# ColorDisplay.net
KiCad netlist of a schematic drawn in EAGLE
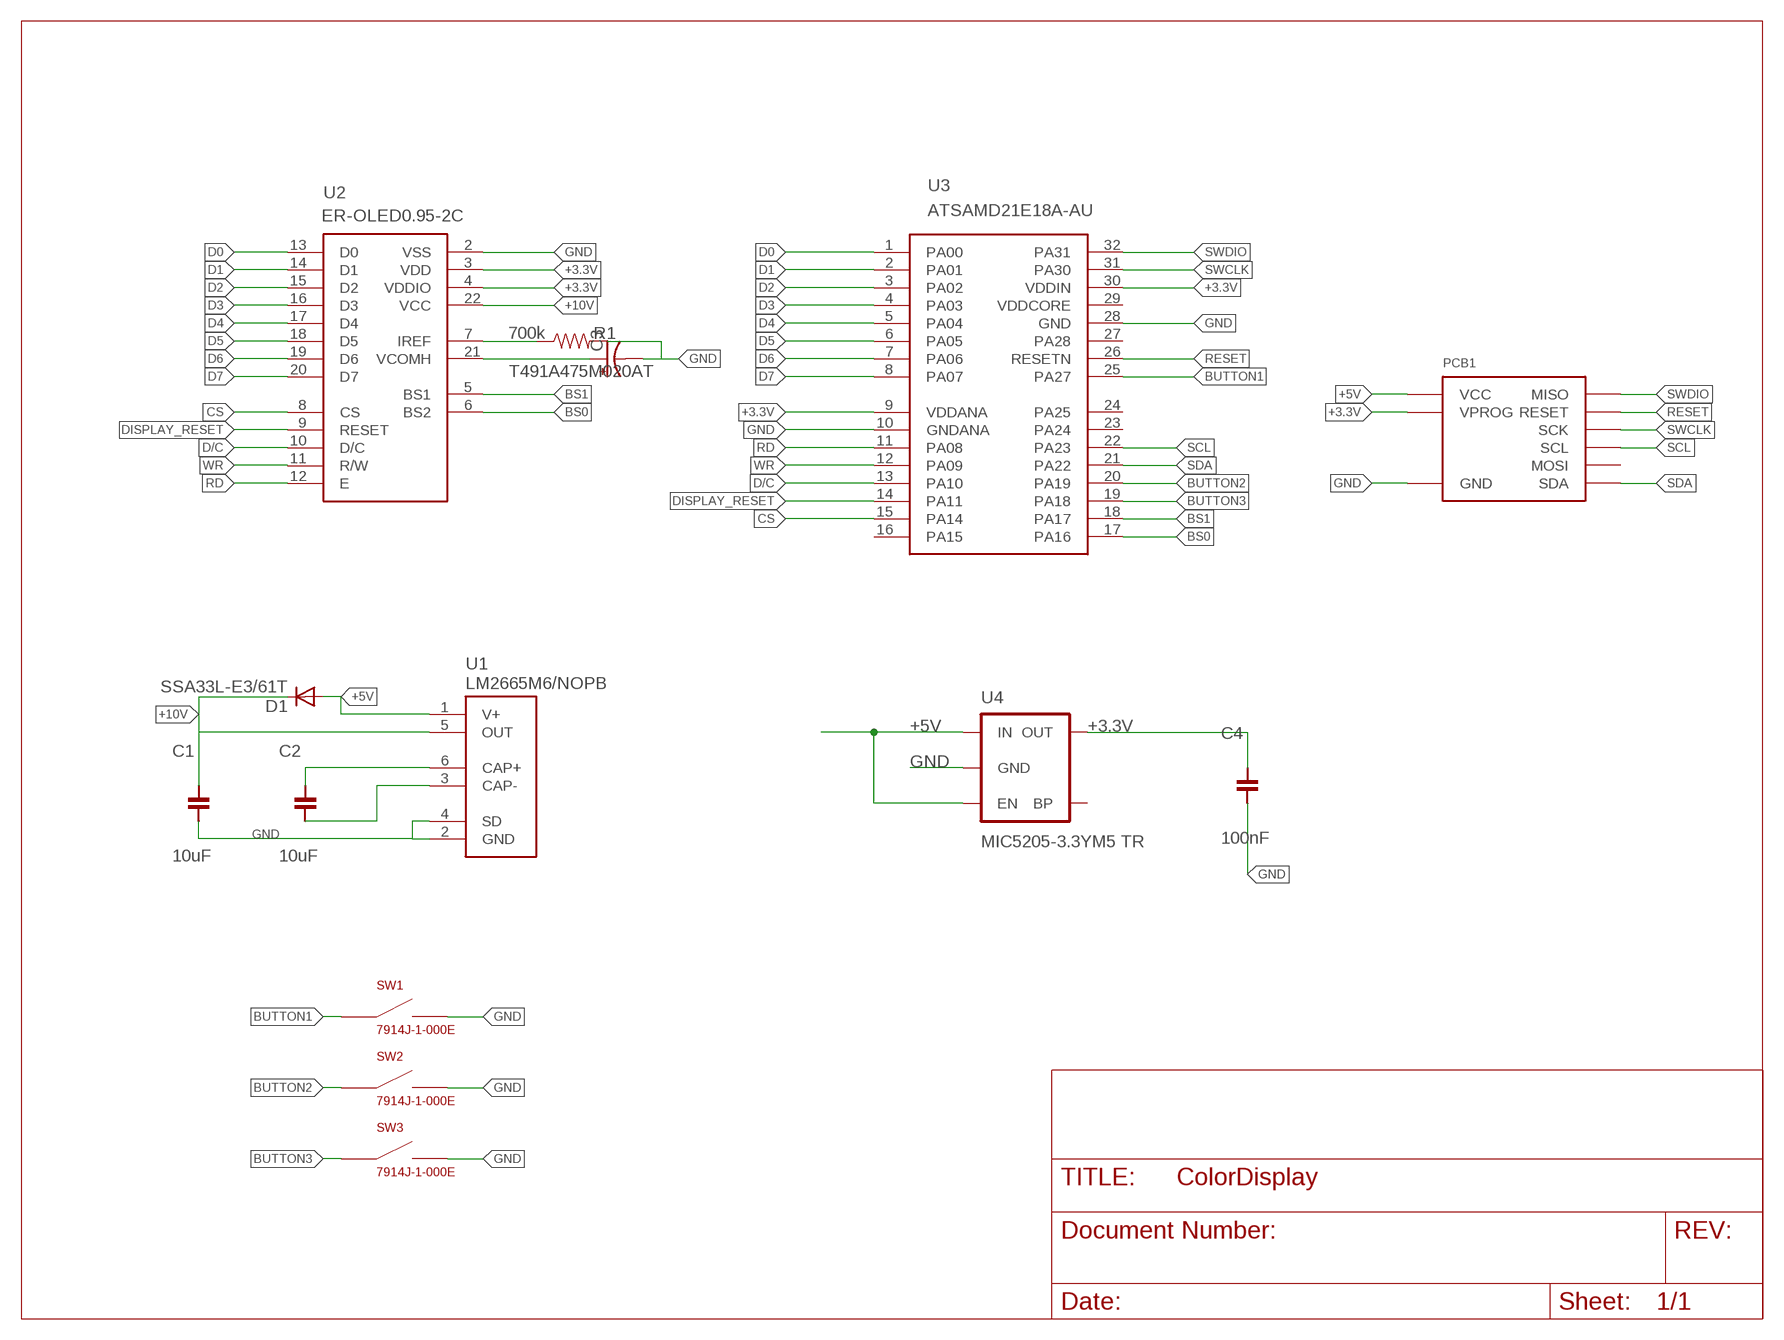
[diagram p0: schematic, sheet 1]

(export (version "E")
  (design (tool "Eeschema 10.0.6"))
  (components
    (comp (ref "C1")
      (value "10uF")
      (footprint "eagle-import:C1206")
      (fields (field (name "PARTNUM") "CL31A106KAHNNNE"))
      (libsource (lib "eagle-import") (part "CAPACITOR-10UF-1206"))
    )
    (comp (ref "C2")
      (value "10uF")
      (footprint "eagle-import:C1206")
      (fields (field (name "PARTNUM") "CL31A106KAHNNNE"))
      (libsource (lib "eagle-import") (part "CAPACITOR-10UF-1206"))
    )
    (comp (ref "C3")
      (value "T491A475M020AT")
      (footprint "eagle-import:EIA3216")
      (libsource (lib "eagle-import") (part "10UF-16V-10%(TANT)"))
    )
    (comp (ref "C4")
      (value "100nF")
      (footprint "eagle-import:0603")
      (fields (field (name "PARTNUM") "C0603C104K5RACTU"))
      (libsource (lib "eagle-import") (part "CAPACITOR-100NF"))
    )
    (comp (ref "D1")
      (value "SSA33L-E3/61T")
      (footprint "eagle-import:SMA-DIODE")
      (libsource (lib "eagle-import") (part "DIODESMA"))
    )
    (comp (ref "PCB1")
      (value "DEVICE-PCB-TABS")
      (footprint "eagle-import:DEVICE-PCB-TABS")
      (fields (field (name "BOARD") "Display") (field (name "VERSION") "2"))
      (libsource (lib "eagle-import") (part "DEVICE-PCB-TABS"))
    )
    (comp (ref "R1")
      (value "700k")
      (footprint "eagle-import:0603")
      (libsource (lib "eagle-import") (part "RESISTOR-0603"))
    )
    (comp (ref "SW1")
      (value "7914J-1-000E")
      (footprint "eagle-import:BOURNS-7914J")
      (libsource (lib "eagle-import") (part "SWITCHBOURNS-7914J"))
    )
    (comp (ref "SW2")
      (value "7914J-1-000E")
      (footprint "eagle-import:BOURNS-7914J")
      (libsource (lib "eagle-import") (part "SWITCHBOURNS-7914J"))
    )
    (comp (ref "SW3")
      (value "7914J-1-000E")
      (footprint "eagle-import:BOURNS-7914J")
      (libsource (lib "eagle-import") (part "SWITCHBOURNS-7914J"))
    )
    (comp (ref "U1")
      (value "LM2665M6/NOPB")
      (footprint "eagle-import:SOT-26")
      (libsource (lib "eagle-import") (part "LM2665"))
    )
    (comp (ref "U2")
      (value "ER-OLED0.95-2C")
      (footprint "eagle-import:FPC-24-REVERSE")
      (fields (field (name "MANUFACTURER") "buydisplay.com"))
      (libsource (lib "eagle-import") (part "OLED-COLORREVERSE"))
    )
    (comp (ref "U3")
      (value "ATSAMD21E18A-AU")
      (footprint "eagle-import:TQFP-32")
      (libsource (lib "eagle-import") (part "SAMD21E"))
    )
    (comp (ref "U4")
      (value "MIC5205-3.3YM5 TR")
      (footprint "eagle-import:SOT23-5")
      (libsource (lib "eagle-import") (part "VREG-MIC5205-3.3V"))
    )
  )
  (nets
    (net (code "1") (name "+3.3V") (class "Default")
      (node (ref "C4") (pin "1") (pinfunction "1_1") (pintype "passive"))
      (node (ref "PCB1") (pin "PROG0") (pinfunction "VPROG_PROG0") (pintype "bidirectional"))
      (node (ref "U2") (pin "3") (pinfunction "VDD_3") (pintype "bidirectional"))
      (node (ref "U2") (pin "4") (pinfunction "VDDIO_4") (pintype "bidirectional"))
      (node (ref "U3") (pin "30") (pinfunction "VDDIN_30") (pintype "bidirectional"))
      (node (ref "U3") (pin "9") (pinfunction "VDDANA_9") (pintype "bidirectional"))
      (node (ref "U4") (pin "5") (pinfunction "OUT_5") (pintype "passive"))
    )
    (net (code "2") (name "+5V") (class "Default")
      (node (ref "D1") (pin "A") (pinfunction "A_A") (pintype "passive"))
      (node (ref "PCB1") (pin "BUS2") (pinfunction "VCC_BUS2") (pintype "bidirectional"))
      (node (ref "U1") (pin "1") (pinfunction "V+_1") (pintype "bidirectional"))
      (node (ref "U4") (pin "1") (pinfunction "IN_1") (pintype "input"))
      (node (ref "U4") (pin "3") (pinfunction "EN_3") (pintype "input"))
    )
    (net (code "3") (name "+10V") (class "Default")
      (node (ref "C1") (pin "1") (pinfunction "1_1") (pintype "passive"))
      (node (ref "D1") (pin "C") (pinfunction "C_C") (pintype "passive"))
      (node (ref "U1") (pin "5") (pinfunction "OUT_5") (pintype "bidirectional"))
      (node (ref "U2") (pin "22") (pinfunction "VCC_22") (pintype "bidirectional"))
    )
    (net (code "4") (name "BS0") (class "Default")
      (node (ref "U2") (pin "6") (pinfunction "BS2_6") (pintype "bidirectional"))
      (node (ref "U3") (pin "17") (pinfunction "PA16_17") (pintype "bidirectional"))
    )
    (net (code "5") (name "BS1") (class "Default")
      (node (ref "U2") (pin "5") (pinfunction "BS1_5") (pintype "bidirectional"))
      (node (ref "U3") (pin "18") (pinfunction "PA17_18") (pintype "bidirectional"))
    )
    (net (code "6") (name "BUTTON1") (class "Default")
      (node (ref "SW1") (pin "POS$1") (pinfunction "POS1_POS$1") (pintype "bidirectional"))
      (node (ref "SW1") (pin "POS$2") (pinfunction "POS1_POS$2") (pintype "bidirectional"))
      (node (ref "U3") (pin "25") (pinfunction "PA27_25") (pintype "bidirectional"))
    )
    (net (code "7") (name "BUTTON2") (class "Default")
      (node (ref "SW2") (pin "POS$1") (pinfunction "POS1_POS$1") (pintype "bidirectional"))
      (node (ref "SW2") (pin "POS$2") (pinfunction "POS1_POS$2") (pintype "bidirectional"))
      (node (ref "U3") (pin "20") (pinfunction "PA19_20") (pintype "bidirectional"))
    )
    (net (code "8") (name "BUTTON3") (class "Default")
      (node (ref "SW3") (pin "POS$1") (pinfunction "POS1_POS$1") (pintype "bidirectional"))
      (node (ref "SW3") (pin "POS$2") (pinfunction "POS1_POS$2") (pintype "bidirectional"))
      (node (ref "U3") (pin "19") (pinfunction "PA18_19") (pintype "bidirectional"))
    )
    (net (code "9") (name "CS") (class "Default")
      (node (ref "U2") (pin "8") (pinfunction "CS_8") (pintype "bidirectional"))
      (node (ref "U3") (pin "15") (pinfunction "PA14_15") (pintype "bidirectional"))
    )
    (net (code "10") (name "D0") (class "Default")
      (node (ref "U2") (pin "13") (pinfunction "D0_13") (pintype "bidirectional"))
      (node (ref "U3") (pin "1") (pinfunction "PA00_1") (pintype "bidirectional"))
    )
    (net (code "11") (name "D1") (class "Default")
      (node (ref "U2") (pin "14") (pinfunction "D1_14") (pintype "bidirectional"))
      (node (ref "U3") (pin "2") (pinfunction "PA01_2") (pintype "bidirectional"))
    )
    (net (code "12") (name "D2") (class "Default")
      (node (ref "U2") (pin "15") (pinfunction "D2_15") (pintype "bidirectional"))
      (node (ref "U3") (pin "3") (pinfunction "PA02_3") (pintype "bidirectional"))
    )
    (net (code "13") (name "D3") (class "Default")
      (node (ref "U2") (pin "16") (pinfunction "D3_16") (pintype "bidirectional"))
      (node (ref "U3") (pin "4") (pinfunction "PA03_4") (pintype "bidirectional"))
    )
    (net (code "14") (name "D4") (class "Default")
      (node (ref "U2") (pin "17") (pinfunction "D4_17") (pintype "bidirectional"))
      (node (ref "U3") (pin "5") (pinfunction "PA04_5") (pintype "bidirectional"))
    )
    (net (code "15") (name "D5") (class "Default")
      (node (ref "U2") (pin "18") (pinfunction "D5_18") (pintype "bidirectional"))
      (node (ref "U3") (pin "6") (pinfunction "PA05_6") (pintype "bidirectional"))
    )
    (net (code "16") (name "D6") (class "Default")
      (node (ref "U2") (pin "19") (pinfunction "D6_19") (pintype "bidirectional"))
      (node (ref "U3") (pin "7") (pinfunction "PA06_7") (pintype "bidirectional"))
    )
    (net (code "17") (name "D7") (class "Default")
      (node (ref "U2") (pin "20") (pinfunction "D7_20") (pintype "bidirectional"))
      (node (ref "U3") (pin "8") (pinfunction "PA07_8") (pintype "bidirectional"))
    )
    (net (code "18") (name "DISPLAY_RESET") (class "Default")
      (node (ref "U2") (pin "9") (pinfunction "RESET_9") (pintype "bidirectional"))
      (node (ref "U3") (pin "14") (pinfunction "PA11_14") (pintype "bidirectional"))
    )
    (net (code "19") (name "D{slash}C") (class "Default")
      (node (ref "U2") (pin "10") (pinfunction "D/C_10") (pintype "bidirectional"))
      (node (ref "U3") (pin "13") (pinfunction "PA10_13") (pintype "bidirectional"))
    )
    (net (code "20") (name "GND") (class "Default")
      (node (ref "C1") (pin "2") (pinfunction "2_2") (pintype "passive"))
      (node (ref "C3") (pin "C") (pinfunction "-_C") (pintype "passive"))
      (node (ref "C4") (pin "2") (pinfunction "2_2") (pintype "passive"))
      (node (ref "PCB1") (pin "BUS0") (pinfunction "GND_BUS0") (pintype "bidirectional"))
      (node (ref "R1") (pin "2") (pinfunction "2_2") (pintype "passive"))
      (node (ref "SW1") (pin "NEG$1") (pinfunction "NEG1_NEG$1") (pintype "bidirectional"))
      (node (ref "SW1") (pin "NEG$2") (pinfunction "NEG1_NEG$2") (pintype "bidirectional"))
      (node (ref "SW2") (pin "NEG$1") (pinfunction "NEG1_NEG$1") (pintype "bidirectional"))
      (node (ref "SW2") (pin "NEG$2") (pinfunction "NEG1_NEG$2") (pintype "bidirectional"))
      (node (ref "SW3") (pin "NEG$1") (pinfunction "NEG1_NEG$1") (pintype "bidirectional"))
      (node (ref "SW3") (pin "NEG$2") (pinfunction "NEG1_NEG$2") (pintype "bidirectional"))
      (node (ref "U1") (pin "2") (pinfunction "GND_2") (pintype "bidirectional"))
      (node (ref "U1") (pin "4") (pinfunction "SD_4") (pintype "bidirectional"))
      (node (ref "U2") (pin "2") (pinfunction "VSS_2") (pintype "bidirectional"))
      (node (ref "U3") (pin "10") (pinfunction "GNDANA_10") (pintype "bidirectional"))
      (node (ref "U3") (pin "28") (pinfunction "GND_28") (pintype "bidirectional"))
      (node (ref "U4") (pin "2") (pinfunction "GND_2") (pintype "input"))
    )
    (net (code "21") (name "Net-(C3-+)") (class "Default")
      (node (ref "C3") (pin "A") (pinfunction "+_A") (pintype "passive"))
      (node (ref "U2") (pin "21") (pinfunction "VCOMH_21") (pintype "bidirectional"))
    )
    (net (code "22") (name "Net-(U1-CAP+)") (class "Default")
      (node (ref "C2") (pin "1") (pinfunction "1_1") (pintype "passive"))
      (node (ref "U1") (pin "6") (pinfunction "CAP+_6") (pintype "bidirectional"))
    )
    (net (code "23") (name "Net-(U1-CAP-)") (class "Default")
      (node (ref "C2") (pin "2") (pinfunction "2_2") (pintype "passive"))
      (node (ref "U1") (pin "3") (pinfunction "CAP-_3") (pintype "bidirectional"))
    )
    (net (code "24") (name "Net-(U2-IREF)") (class "Default")
      (node (ref "R1") (pin "1") (pinfunction "1_1") (pintype "passive"))
      (node (ref "U2") (pin "7") (pinfunction "IREF_7") (pintype "bidirectional"))
    )
    (net (code "25") (name "RD") (class "Default")
      (node (ref "U2") (pin "12") (pinfunction "E_12") (pintype "bidirectional"))
      (node (ref "U3") (pin "11") (pinfunction "PA08_11") (pintype "bidirectional"))
    )
    (net (code "26") (name "RESET") (class "Default")
      (node (ref "PCB1") (pin "PROG1") (pinfunction "RESET_PROG1") (pintype "bidirectional"))
      (node (ref "U3") (pin "26") (pinfunction "RESETN_26") (pintype "bidirectional"))
    )
    (net (code "27") (name "SCL") (class "Default")
      (node (ref "PCB1") (pin "BUS3") (pinfunction "SCL_BUS3") (pintype "bidirectional"))
      (node (ref "U3") (pin "22") (pinfunction "PA23_22") (pintype "bidirectional"))
    )
    (net (code "28") (name "SDA") (class "Default")
      (node (ref "PCB1") (pin "BUS1") (pinfunction "SDA_BUS1") (pintype "bidirectional"))
      (node (ref "U3") (pin "21") (pinfunction "PA22_21") (pintype "bidirectional"))
    )
    (net (code "29") (name "SWCLK") (class "Default")
      (node (ref "PCB1") (pin "PROG2") (pinfunction "SCK_PROG2") (pintype "bidirectional"))
      (node (ref "U3") (pin "31") (pinfunction "PA30_31") (pintype "bidirectional"))
    )
    (net (code "30") (name "SWDIO") (class "Default")
      (node (ref "PCB1") (pin "PROG3") (pinfunction "MISO_PROG3") (pintype "bidirectional"))
      (node (ref "U3") (pin "32") (pinfunction "PA31_32") (pintype "bidirectional"))
    )
    (net (code "31") (name "WR") (class "Default")
      (node (ref "U2") (pin "11") (pinfunction "R/W_11") (pintype "bidirectional"))
      (node (ref "U3") (pin "12") (pinfunction "PA09_12") (pintype "bidirectional"))
    )
    (net (code "32") (name "unconnected-(PCB1-MOSI-PadPROG4)") (class "Default")
      (node (ref "PCB1") (pin "PROG4") (pinfunction "MOSI_PROG4") (pintype "bidirectional"))
    )
    (net (code "33") (name "unconnected-(U3-PA15-Pad16)") (class "Default")
      (node (ref "U3") (pin "16") (pinfunction "PA15_16") (pintype "bidirectional"))
    )
    (net (code "34") (name "unconnected-(U3-PA24-Pad23)") (class "Default")
      (node (ref "U3") (pin "23") (pinfunction "PA24_23") (pintype "bidirectional"))
    )
    (net (code "35") (name "unconnected-(U3-PA25-Pad24)") (class "Default")
      (node (ref "U3") (pin "24") (pinfunction "PA25_24") (pintype "bidirectional"))
    )
    (net (code "36") (name "unconnected-(U3-PA28-Pad27)") (class "Default")
      (node (ref "U3") (pin "27") (pinfunction "PA28_27") (pintype "bidirectional"))
    )
    (net (code "37") (name "unconnected-(U3-VDDCORE-Pad29)") (class "Default")
      (node (ref "U3") (pin "29") (pinfunction "VDDCORE_29") (pintype "bidirectional"))
    )
    (net (code "38") (name "unconnected-(U4-BP-Pad4)") (class "Default")
      (node (ref "U4") (pin "4") (pinfunction "BP_4") (pintype "input"))
    )
  )
)
